# balun.net
KiCad netlist of a schematic drawn in Altium Designer
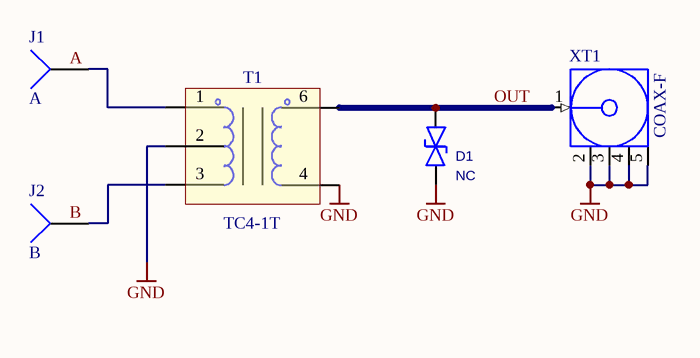
[diagram p0: balun.SchDoc]

(export (version "E")
  (design (tool "Eeschema 10.0.6"))
  (components
    (comp (ref "D1")
      (value "NC")
      (footprint "SOD-323")
      (description "TVS Diodes")
      (libsource (lib "diodes") (part "TVS_BIDIR"))
    )
    (comp (ref "J1")
      (value "A")
      (footprint "PIN1")
      (description "Socket")
      (fields (field (name "PUBLISHER") "Altium Limited"))
      (libsource (lib "Miscellaneous Connectors") (part "Socket"))
    )
    (comp (ref "J2")
      (value "B")
      (footprint "PIN1")
      (description "Socket")
      (fields (field (name "PUBLISHER") "Altium Limited"))
      (libsource (lib "Miscellaneous Connectors") (part "Socket"))
    )
    (comp (ref "T1")
      (value "TC4-1T")
      (footprint "AT224")
      (description "RF TRANSFORMERS WIDEBAND")
      (libsource (lib "TR-RF-WB") (part "TC4-1T"))
    )
    (comp (ref "XT1")
      (value "COAX-F")
      (footprint "RF:SMA-16")
      (fields (field (name "PUBLISHER") "Altium Limited"))
      (libsource (lib "Miscellaneous Connectors") (part "COAX-F"))
    )
  )
  (nets
    (net (code "3") (name "/OUT") (class "Default")
      (node (ref "D1") (pin "2") (pinfunction "2_2") (pintype "passive"))
      (node (ref "T1") (pin "6") (pinfunction "6_6") (pintype "passive"))
      (node (ref "XT1") (pin "1") (pinfunction "Signal_1") (pintype "input"))
    )
    (net (code "4") (name "GND") (class "Default")
      (node (ref "D1") (pin "1") (pinfunction "1_1") (pintype "passive"))
      (node (ref "T1") (pin "2") (pinfunction "2_2") (pintype "passive"))
      (node (ref "T1") (pin "4") (pinfunction "4_4") (pintype "passive"))
      (node (ref "XT1") (pin "2") (pinfunction "GND_2") (pintype "power_in"))
      (node (ref "XT1") (pin "3") (pinfunction "GND_3") (pintype "power_in"))
      (node (ref "XT1") (pin "4") (pinfunction "GND_4") (pintype "power_in"))
      (node (ref "XT1") (pin "5") (pinfunction "GND_5") (pintype "power_in"))
    )
    (net (code "5") (name "Net-(J1-Pad1)") (class "Default")
      (node (ref "J1") (pin "1") (pinfunction "1_1") (pintype "passive"))
      (node (ref "T1") (pin "1") (pinfunction "1_1") (pintype "passive"))
    )
    (net (code "6") (name "Net-(J2-Pad1)") (class "Default")
      (node (ref "J2") (pin "1") (pinfunction "1_1") (pintype "passive"))
      (node (ref "T1") (pin "3") (pinfunction "3_3") (pintype "passive"))
    )
  )
)
